# di.net
KiCad netlist of a schematic drawn in Altium Designer
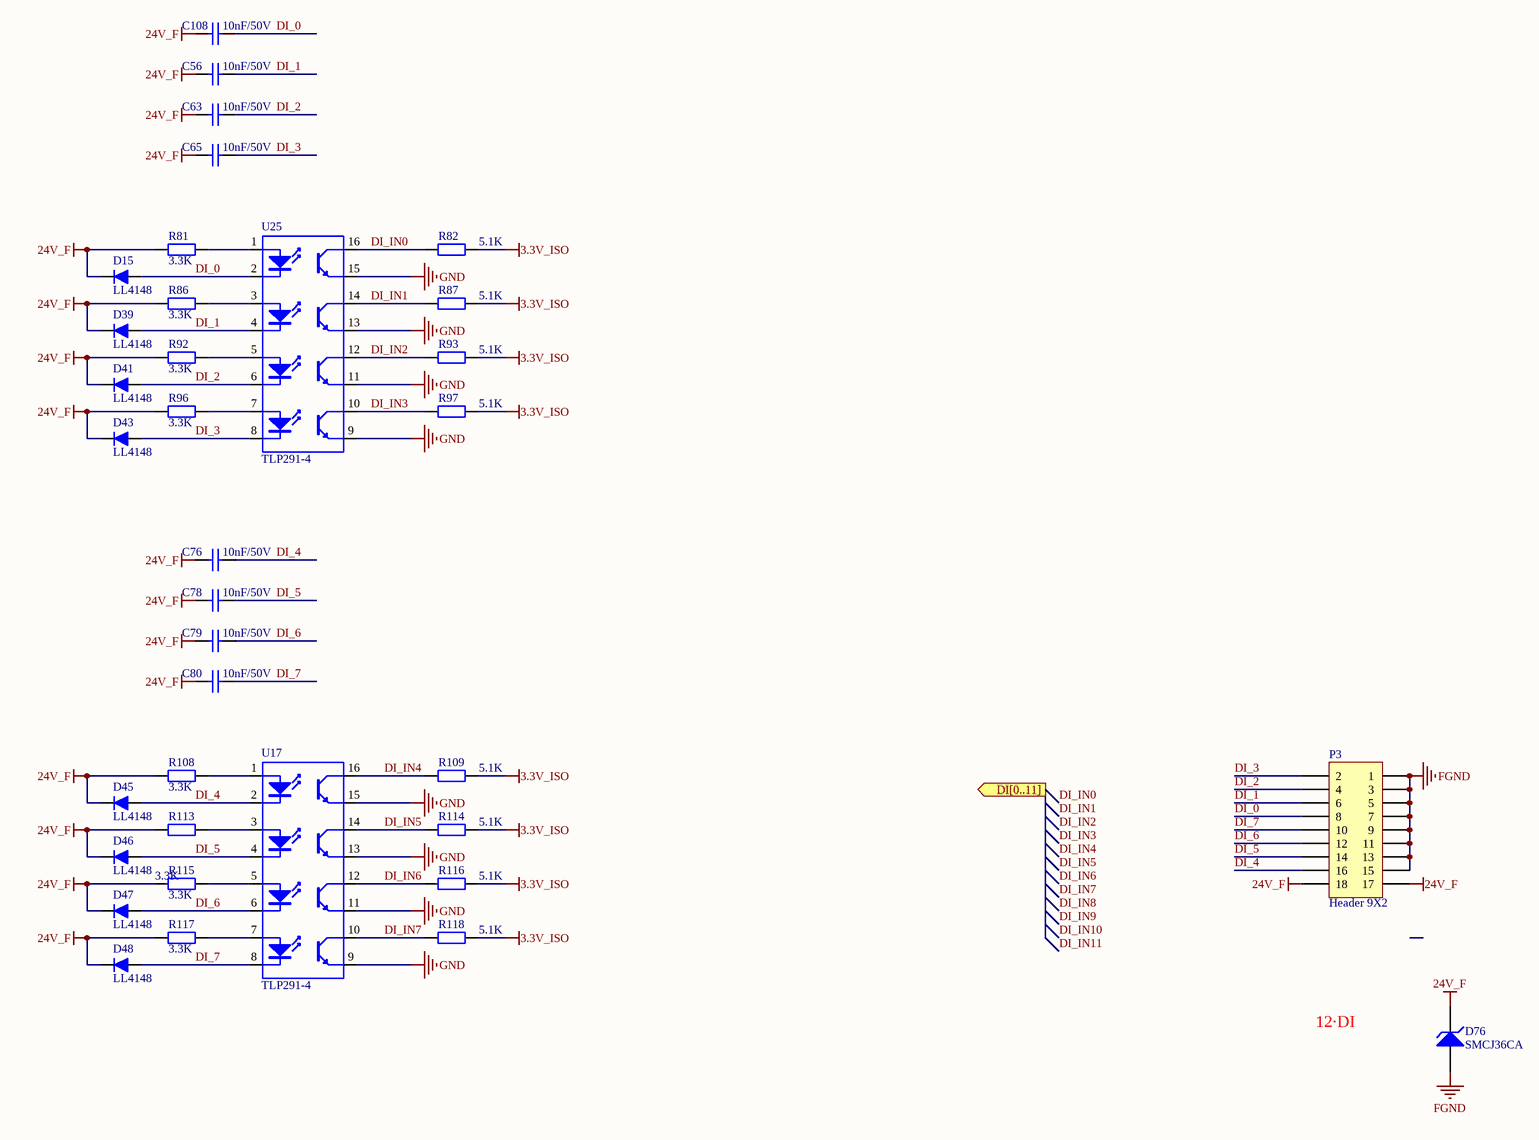
[diagram p0: di.SchDoc]

(export (version "E")
  (design (tool "Eeschema 10.0.6"))
  (components
    (comp (ref "C56")
      (value "10nF/50V")
      (footprint "0603C")
      (description "Capacitor")
      (fields (field (name "PUBLISHER") "Altium Limited"))
      (libsource (lib "Miscellaneous Devices") (part "Cap"))
    )
    (comp (ref "C63")
      (value "10nF/50V")
      (footprint "0603C")
      (description "Capacitor")
      (fields (field (name "PUBLISHER") "Altium Limited"))
      (libsource (lib "Miscellaneous Devices") (part "Cap"))
    )
    (comp (ref "C65")
      (value "10nF/50V")
      (footprint "0603C")
      (description "Capacitor")
      (fields (field (name "PUBLISHER") "Altium Limited"))
      (libsource (lib "Miscellaneous Devices") (part "Cap"))
    )
    (comp (ref "C76")
      (value "10nF/50V")
      (footprint "0603C")
      (description "Capacitor")
      (fields (field (name "PUBLISHER") "Altium Limited"))
      (libsource (lib "Miscellaneous Devices") (part "Cap"))
    )
    (comp (ref "C78")
      (value "10nF/50V")
      (footprint "0603C")
      (description "Capacitor")
      (fields (field (name "PUBLISHER") "Altium Limited"))
      (libsource (lib "Miscellaneous Devices") (part "Cap"))
    )
    (comp (ref "C79")
      (value "10nF/50V")
      (footprint "0603C")
      (description "Capacitor")
      (fields (field (name "PUBLISHER") "Altium Limited"))
      (libsource (lib "Miscellaneous Devices") (part "Cap"))
    )
    (comp (ref "C80")
      (value "10nF/50V")
      (footprint "0603C")
      (description "Capacitor")
      (fields (field (name "PUBLISHER") "Altium Limited"))
      (libsource (lib "Miscellaneous Devices") (part "Cap"))
    )
    (comp (ref "C108")
      (value "10nF/50V")
      (footprint "0603C")
      (description "Capacitor")
      (fields (field (name "PUBLISHER") "Altium Limited"))
      (libsource (lib "Miscellaneous Devices") (part "Cap"))
    )
    (comp (ref "D15")
      (value "LL4148")
      (footprint "DO-213AB/LL34/MiniMELF")
      (description "VISHAY,LL4148,圆柱体MiniMELF100V/2A,ROHS")
      (libsource (lib "controller_V1.1") (part "LL4148"))
    )
    (comp (ref "D39")
      (value "LL4148")
      (footprint "DO-213AB/LL34/MiniMELF")
      (description "VISHAY,LL4148,圆柱体MiniMELF100V/2A,ROHS")
      (libsource (lib "controller_V1.1") (part "LL4148"))
    )
    (comp (ref "D41")
      (value "LL4148")
      (footprint "DO-213AB/LL34/MiniMELF")
      (description "VISHAY,LL4148,圆柱体MiniMELF100V/2A,ROHS")
      (libsource (lib "controller_V1.1") (part "LL4148"))
    )
    (comp (ref "D43")
      (value "LL4148")
      (footprint "DO-213AB/LL34/MiniMELF")
      (description "VISHAY,LL4148,圆柱体MiniMELF100V/2A,ROHS")
      (libsource (lib "controller_V1.1") (part "LL4148"))
    )
    (comp (ref "D45")
      (value "LL4148")
      (footprint "DO-213AB/LL34/MiniMELF")
      (description "VISHAY,LL4148,圆柱体MiniMELF100V/2A,ROHS")
      (libsource (lib "controller_V1.1") (part "LL4148"))
    )
    (comp (ref "D46")
      (value "LL4148")
      (footprint "DO-213AB/LL34/MiniMELF")
      (description "VISHAY,LL4148,圆柱体MiniMELF100V/2A,ROHS")
      (libsource (lib "controller_V1.1") (part "LL4148"))
    )
    (comp (ref "D47")
      (value "LL4148")
      (footprint "DO-213AB/LL34/MiniMELF")
      (description "VISHAY,LL4148,圆柱体MiniMELF100V/2A,ROHS")
      (libsource (lib "controller_V1.1") (part "LL4148"))
    )
    (comp (ref "D48")
      (value "LL4148")
      (footprint "DO-213AB/LL34/MiniMELF")
      (description "VISHAY,LL4148,圆柱体MiniMELF100V/2A,ROHS")
      (libsource (lib "controller_V1.1") (part "LL4148"))
    )
    (comp (ref "D76")
      (value "SMCJ36CA")
      (footprint "smc")
      (description "SMBJ36CA")
      (fields (field (name "PUBLISHER") "Altium Limited"))
      (libsource (lib "Miscellaneous Devices") (part "D Zener"))
    )
    (comp (ref "P3")
      (value "Header 9X2")
      (footprint "XH2.54_2x9")
      (description "Header, 9-Pin, Dual row")
      (fields (field (name "PUBLISHER") "Altium Limited"))
      (libsource (lib "Miscellaneous Connectors") (part "Header 9X2"))
    )
    (comp (ref "R81") (value "3.3K") (footprint "0603R") (libsource (lib "MQlibrary") (part "Res0805M")))
    (comp (ref "R82") (value "5.1K") (footprint "0603R") (libsource (lib "MQlibrary") (part "Res0805M")))
    (comp (ref "R86") (value "3.3K") (footprint "0603R") (libsource (lib "MQlibrary") (part "Res0805M")))
    (comp (ref "R87") (value "5.1K") (footprint "0603R") (libsource (lib "MQlibrary") (part "Res0805M")))
    (comp (ref "R92") (value "3.3K") (footprint "0603R") (libsource (lib "MQlibrary") (part "Res0805M")))
    (comp (ref "R93") (value "5.1K") (footprint "0603R") (libsource (lib "MQlibrary") (part "Res0805M")))
    (comp (ref "R96") (value "3.3K") (footprint "0603R") (libsource (lib "MQlibrary") (part "Res0805M")))
    (comp (ref "R97") (value "5.1K") (footprint "0603R") (libsource (lib "MQlibrary") (part "Res0805M")))
    (comp (ref "R108") (value "3.3K") (footprint "0603R") (libsource (lib "MQlibrary") (part "Res0805M")))
    (comp (ref "R109") (value "5.1K") (footprint "0603R") (libsource (lib "MQlibrary") (part "Res0805M")))
    (comp (ref "R113") (value "3.3K") (footprint "0603R") (libsource (lib "MQlibrary") (part "Res0805M")))
    (comp (ref "R114") (value "5.1K") (footprint "0603R") (libsource (lib "MQlibrary") (part "Res0805M")))
    (comp (ref "R115") (value "3.3K") (footprint "0603R") (libsource (lib "MQlibrary") (part "Res0805M")))
    (comp (ref "R116") (value "5.1K") (footprint "0603R") (libsource (lib "MQlibrary") (part "Res0805M")))
    (comp (ref "R117") (value "3.3K") (footprint "0603R") (libsource (lib "MQlibrary") (part "Res0805M")))
    (comp (ref "R118") (value "5.1K") (footprint "0603R") (libsource (lib "MQlibrary") (part "Res0805M")))
    (comp (ref "U17") (value "TLP291-4") (footprint "SOP16-T") (libsource (lib "DI16") (part "TLP281-4")))
    (comp (ref "U25") (value "TLP291-4") (footprint "SOP16-T") (libsource (lib "DI16") (part "TLP281-4")))
  )
  (nets
    (net (code "14") (name "/DI_0") (class "Default")
      (node (ref "C108") (pin "2") (pinfunction "2_2") (pintype "passive"))
      (node (ref "D15") (pin "1") (pinfunction "A_1") (pintype "passive"))
      (node (ref "P3") (pin "8") (pinfunction "8_8") (pintype "passive"))
      (node (ref "U25") (pin "2") (pinfunction "K_2") (pintype "passive"))
    )
    (net (code "15") (name "/DI_1") (class "Default")
      (node (ref "C56") (pin "2") (pinfunction "2_2") (pintype "passive"))
      (node (ref "D39") (pin "1") (pinfunction "A_1") (pintype "passive"))
      (node (ref "P3") (pin "6") (pinfunction "6_6") (pintype "passive"))
      (node (ref "U25") (pin "4") (pinfunction "K_4") (pintype "passive"))
    )
    (net (code "16") (name "/DI_2") (class "Default")
      (node (ref "C63") (pin "2") (pinfunction "2_2") (pintype "passive"))
      (node (ref "D41") (pin "1") (pinfunction "A_1") (pintype "passive"))
      (node (ref "P3") (pin "4") (pinfunction "4_4") (pintype "passive"))
      (node (ref "U25") (pin "6") (pinfunction "K_6") (pintype "passive"))
    )
    (net (code "17") (name "/DI_3") (class "Default")
      (node (ref "C65") (pin "2") (pinfunction "2_2") (pintype "passive"))
      (node (ref "D43") (pin "1") (pinfunction "A_1") (pintype "passive"))
      (node (ref "P3") (pin "2") (pinfunction "2_2") (pintype "passive"))
      (node (ref "U25") (pin "8") (pinfunction "K_8") (pintype "passive"))
    )
    (net (code "18") (name "/DI_4") (class "Default")
      (node (ref "C76") (pin "2") (pinfunction "2_2") (pintype "passive"))
      (node (ref "D45") (pin "1") (pinfunction "A_1") (pintype "passive"))
      (node (ref "P3") (pin "16") (pinfunction "16_16") (pintype "passive"))
      (node (ref "U17") (pin "2") (pinfunction "K_2") (pintype "passive"))
    )
    (net (code "19") (name "/DI_5") (class "Default")
      (node (ref "C78") (pin "2") (pinfunction "2_2") (pintype "passive"))
      (node (ref "D46") (pin "1") (pinfunction "A_1") (pintype "passive"))
      (node (ref "P3") (pin "14") (pinfunction "14_14") (pintype "passive"))
      (node (ref "U17") (pin "4") (pinfunction "K_4") (pintype "passive"))
    )
    (net (code "20") (name "/DI_6") (class "Default")
      (node (ref "C79") (pin "2") (pinfunction "2_2") (pintype "passive"))
      (node (ref "D47") (pin "1") (pinfunction "A_1") (pintype "passive"))
      (node (ref "P3") (pin "12") (pinfunction "12_12") (pintype "passive"))
      (node (ref "U17") (pin "6") (pinfunction "K_6") (pintype "passive"))
    )
    (net (code "21") (name "/DI_7") (class "Default")
      (node (ref "C80") (pin "2") (pinfunction "2_2") (pintype "passive"))
      (node (ref "D48") (pin "1") (pinfunction "A_1") (pintype "passive"))
      (node (ref "P3") (pin "10") (pinfunction "10_10") (pintype "passive"))
      (node (ref "U17") (pin "8") (pinfunction "K_8") (pintype "passive"))
    )
    (net (code "22") (name "/DI_IN0") (class "Default")
      (node (ref "R82") (pin "2") (pinfunction "2_2") (pintype "passive"))
      (node (ref "U25") (pin "16") (pinfunction "C_16") (pintype "passive"))
    )
    (net (code "23") (name "/DI_IN1") (class "Default")
      (node (ref "R87") (pin "2") (pinfunction "2_2") (pintype "passive"))
      (node (ref "U25") (pin "14") (pinfunction "C_14") (pintype "passive"))
    )
    (net (code "24") (name "/DI_IN2") (class "Default")
      (node (ref "R93") (pin "2") (pinfunction "2_2") (pintype "passive"))
      (node (ref "U25") (pin "12") (pinfunction "C_12") (pintype "passive"))
    )
    (net (code "25") (name "/DI_IN3") (class "Default")
      (node (ref "R97") (pin "2") (pinfunction "2_2") (pintype "passive"))
      (node (ref "U25") (pin "10") (pinfunction "C_10") (pintype "passive"))
    )
    (net (code "26") (name "/DI_IN4") (class "Default")
      (node (ref "R109") (pin "2") (pinfunction "2_2") (pintype "passive"))
      (node (ref "U17") (pin "16") (pinfunction "C_16") (pintype "passive"))
    )
    (net (code "27") (name "/DI_IN5") (class "Default")
      (node (ref "R114") (pin "2") (pinfunction "2_2") (pintype "passive"))
      (node (ref "U17") (pin "14") (pinfunction "C_14") (pintype "passive"))
    )
    (net (code "28") (name "/DI_IN6") (class "Default")
      (node (ref "R116") (pin "2") (pinfunction "2_2") (pintype "passive"))
      (node (ref "U17") (pin "12") (pinfunction "C_12") (pintype "passive"))
    )
    (net (code "29") (name "/DI_IN7") (class "Default")
      (node (ref "R118") (pin "2") (pinfunction "2_2") (pintype "passive"))
      (node (ref "U17") (pin "10") (pinfunction "C_10") (pintype "passive"))
    )
    (net (code "34") (name "3.3V_ISO") (class "Default")
      (node (ref "R109") (pin "1") (pinfunction "1_1") (pintype "passive"))
      (node (ref "R114") (pin "1") (pinfunction "1_1") (pintype "passive"))
      (node (ref "R116") (pin "1") (pinfunction "1_1") (pintype "passive"))
      (node (ref "R118") (pin "1") (pinfunction "1_1") (pintype "passive"))
      (node (ref "R82") (pin "1") (pinfunction "1_1") (pintype "passive"))
      (node (ref "R87") (pin "1") (pinfunction "1_1") (pintype "passive"))
      (node (ref "R93") (pin "1") (pinfunction "1_1") (pintype "passive"))
      (node (ref "R97") (pin "1") (pinfunction "1_1") (pintype "passive"))
    )
    (net (code "35") (name "24V_F") (class "Default")
      (node (ref "C108") (pin "1") (pinfunction "1_1") (pintype "passive"))
      (node (ref "C56") (pin "1") (pinfunction "1_1") (pintype "passive"))
      (node (ref "C63") (pin "1") (pinfunction "1_1") (pintype "passive"))
      (node (ref "C65") (pin "1") (pinfunction "1_1") (pintype "passive"))
      (node (ref "C76") (pin "1") (pinfunction "1_1") (pintype "passive"))
      (node (ref "C78") (pin "1") (pinfunction "1_1") (pintype "passive"))
      (node (ref "C79") (pin "1") (pinfunction "1_1") (pintype "passive"))
      (node (ref "C80") (pin "1") (pinfunction "1_1") (pintype "passive"))
      (node (ref "D15") (pin "2") (pinfunction "K_2") (pintype "passive"))
      (node (ref "D39") (pin "2") (pinfunction "K_2") (pintype "passive"))
      (node (ref "D41") (pin "2") (pinfunction "K_2") (pintype "passive"))
      (node (ref "D43") (pin "2") (pinfunction "K_2") (pintype "passive"))
      (node (ref "D45") (pin "2") (pinfunction "K_2") (pintype "passive"))
      (node (ref "D46") (pin "2") (pinfunction "K_2") (pintype "passive"))
      (node (ref "D47") (pin "2") (pinfunction "K_2") (pintype "passive"))
      (node (ref "D48") (pin "2") (pinfunction "K_2") (pintype "passive"))
      (node (ref "D76") (pin "2") (pinfunction "K_2") (pintype "passive"))
      (node (ref "P3") (pin "17") (pinfunction "17_17") (pintype "passive"))
      (node (ref "P3") (pin "18") (pinfunction "18_18") (pintype "passive"))
      (node (ref "R108") (pin "2") (pinfunction "2_2") (pintype "passive"))
      (node (ref "R113") (pin "2") (pinfunction "2_2") (pintype "passive"))
      (node (ref "R115") (pin "2") (pinfunction "2_2") (pintype "passive"))
      (node (ref "R117") (pin "2") (pinfunction "2_2") (pintype "passive"))
      (node (ref "R81") (pin "2") (pinfunction "2_2") (pintype "passive"))
      (node (ref "R86") (pin "2") (pinfunction "2_2") (pintype "passive"))
      (node (ref "R92") (pin "2") (pinfunction "2_2") (pintype "passive"))
      (node (ref "R96") (pin "2") (pinfunction "2_2") (pintype "passive"))
    )
    (net (code "36") (name "FGND") (class "Default")
      (node (ref "D76") (pin "1") (pinfunction "A_1") (pintype "passive"))
      (node (ref "P3") (pin "1") (pinfunction "1_1") (pintype "passive"))
      (node (ref "P3") (pin "11") (pinfunction "11_11") (pintype "passive"))
      (node (ref "P3") (pin "13") (pinfunction "13_13") (pintype "passive"))
      (node (ref "P3") (pin "15") (pinfunction "15_15") (pintype "passive"))
      (node (ref "P3") (pin "3") (pinfunction "3_3") (pintype "passive"))
      (node (ref "P3") (pin "5") (pinfunction "5_5") (pintype "passive"))
      (node (ref "P3") (pin "7") (pinfunction "7_7") (pintype "passive"))
      (node (ref "P3") (pin "9") (pinfunction "9_9") (pintype "passive"))
    )
    (net (code "37") (name "GND") (class "Default")
      (node (ref "U17") (pin "11") (pinfunction "E_11") (pintype "passive"))
      (node (ref "U17") (pin "13") (pinfunction "E_13") (pintype "passive"))
      (node (ref "U17") (pin "15") (pinfunction "E_15") (pintype "passive"))
      (node (ref "U17") (pin "9") (pinfunction "E_9") (pintype "passive"))
      (node (ref "U25") (pin "11") (pinfunction "E_11") (pintype "passive"))
      (node (ref "U25") (pin "13") (pinfunction "E_13") (pintype "passive"))
      (node (ref "U25") (pin "15") (pinfunction "E_15") (pintype "passive"))
      (node (ref "U25") (pin "9") (pinfunction "E_9") (pintype "passive"))
    )
    (net (code "38") (name "Net-(R81-Pad1)") (class "Default")
      (node (ref "R81") (pin "1") (pinfunction "1_1") (pintype "passive"))
      (node (ref "U25") (pin "1") (pinfunction "A_1") (pintype "passive"))
    )
    (net (code "39") (name "Net-(R86-Pad1)") (class "Default")
      (node (ref "R86") (pin "1") (pinfunction "1_1") (pintype "passive"))
      (node (ref "U25") (pin "3") (pinfunction "A_3") (pintype "passive"))
    )
    (net (code "40") (name "Net-(R92-Pad1)") (class "Default")
      (node (ref "R92") (pin "1") (pinfunction "1_1") (pintype "passive"))
      (node (ref "U25") (pin "5") (pinfunction "A_5") (pintype "passive"))
    )
    (net (code "41") (name "Net-(R96-Pad1)") (class "Default")
      (node (ref "R96") (pin "1") (pinfunction "1_1") (pintype "passive"))
      (node (ref "U25") (pin "7") (pinfunction "A_7") (pintype "passive"))
    )
    (net (code "42") (name "Net-(R108-Pad1)") (class "Default")
      (node (ref "R108") (pin "1") (pinfunction "1_1") (pintype "passive"))
      (node (ref "U17") (pin "1") (pinfunction "A_1") (pintype "passive"))
    )
    (net (code "43") (name "Net-(R113-Pad1)") (class "Default")
      (node (ref "R113") (pin "1") (pinfunction "1_1") (pintype "passive"))
      (node (ref "U17") (pin "3") (pinfunction "A_3") (pintype "passive"))
    )
    (net (code "44") (name "Net-(R115-Pad1)") (class "Default")
      (node (ref "R115") (pin "1") (pinfunction "1_1") (pintype "passive"))
      (node (ref "U17") (pin "5") (pinfunction "A_5") (pintype "passive"))
    )
    (net (code "45") (name "Net-(R117-Pad1)") (class "Default")
      (node (ref "R117") (pin "1") (pinfunction "1_1") (pintype "passive"))
      (node (ref "U17") (pin "7") (pinfunction "A_7") (pintype "passive"))
    )
  )
)
